# Control.net
KiCad netlist of a schematic drawn in Altium Designer
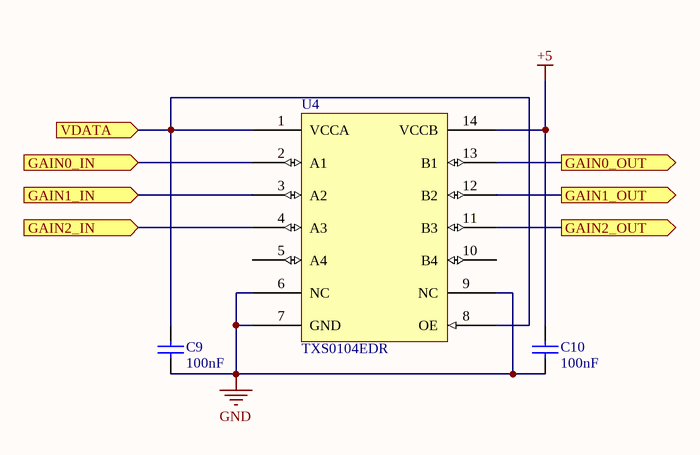
[diagram p0: Control.SchDoc]

(export (version "E")
  (design (tool "Eeschema 10.0.6"))
  (components
    (comp (ref "C9")
      (value "100nF")
      (footprint "CAPC1608X10M")
      (description "GRM188 0603(1.6mm*0.8mm) ±5% and ±10% (15pF-2.2uF) SMD Capacitor")
      (fields (field (name "PUBLISHER") "Altium Limited"))
      (libsource (lib "Acoustics") (part "GRM188"))
    )
    (comp (ref "C10")
      (value "100nF")
      (footprint "CAPC1608X10M")
      (description "GRM188 0603(1.6mm*0.8mm) ±5% and ±10% (15pF-2.2uF) SMD Capacitor")
      (fields (field (name "PUBLISHER") "Altium Limited"))
      (libsource (lib "Acoustics") (part "GRM188"))
    )
    (comp (ref "U4")
      (value "TXS0104EDR")
      (footprint "SOIC127P600X175-14M")
      (description "Voltage Level Translator Bidirectional 1 Circuit 4 Channel 24Mbps 14-SOIC")
      (libsource (lib "Acoustics") (part "TXS0104EDR"))
    )
  )
  (nets
    (net (code "1") (name "+5") (class "Default")
      (node (ref "C10") (pin "2") (pinfunction "2_2") (pintype "passive"))
      (node (ref "U4") (pin "14") (pinfunction "VCCB_14") (pintype "power_in"))
    )
    (net (code "2") (name "/GAIN0_IN") (class "Default")
      (node (ref "U4") (pin "2") (pinfunction "A1_2") (pintype "bidirectional"))
    )
    (net (code "3") (name "/GAIN0_OUT") (class "Default")
      (node (ref "U4") (pin "13") (pinfunction "B1_13") (pintype "bidirectional"))
    )
    (net (code "4") (name "/GAIN1_IN") (class "Default")
      (node (ref "U4") (pin "3") (pinfunction "A2_3") (pintype "bidirectional"))
    )
    (net (code "5") (name "/GAIN1_OUT") (class "Default")
      (node (ref "U4") (pin "12") (pinfunction "B2_12") (pintype "bidirectional"))
    )
    (net (code "6") (name "/GAIN2_IN") (class "Default")
      (node (ref "U4") (pin "4") (pinfunction "A3_4") (pintype "bidirectional"))
    )
    (net (code "7") (name "/GAIN2_OUT") (class "Default")
      (node (ref "U4") (pin "11") (pinfunction "B3_11") (pintype "bidirectional"))
    )
    (net (code "8") (name "/VDATA") (class "Default")
      (node (ref "C9") (pin "2") (pinfunction "2_2") (pintype "passive"))
      (node (ref "U4") (pin "1") (pinfunction "VCCA_1") (pintype "power_in"))
      (node (ref "U4") (pin "8") (pinfunction "OE_8") (pintype "input"))
    )
    (net (code "9") (name "GND") (class "Default")
      (node (ref "C10") (pin "1") (pinfunction "1_1") (pintype "passive"))
      (node (ref "C9") (pin "1") (pinfunction "1_1") (pintype "passive"))
      (node (ref "U4") (pin "6") (pinfunction "NC_6") (pintype "power_in"))
      (node (ref "U4") (pin "7") (pinfunction "GND_7") (pintype "power_in"))
      (node (ref "U4") (pin "9") (pinfunction "NC_9") (pintype "power_in"))
    )
    (net (code "10") (name "unconnected-(U4-A4-Pad5)") (class "Default")
      (node (ref "U4") (pin "5") (pinfunction "A4_5") (pintype "bidirectional"))
    )
    (net (code "11") (name "unconnected-(U4-B4-Pad10)") (class "Default")
      (node (ref "U4") (pin "10") (pinfunction "B4_10") (pintype "bidirectional"))
    )
  )
)
